# MFX.net
KiCad netlist of a schematic drawn in Altium Designer
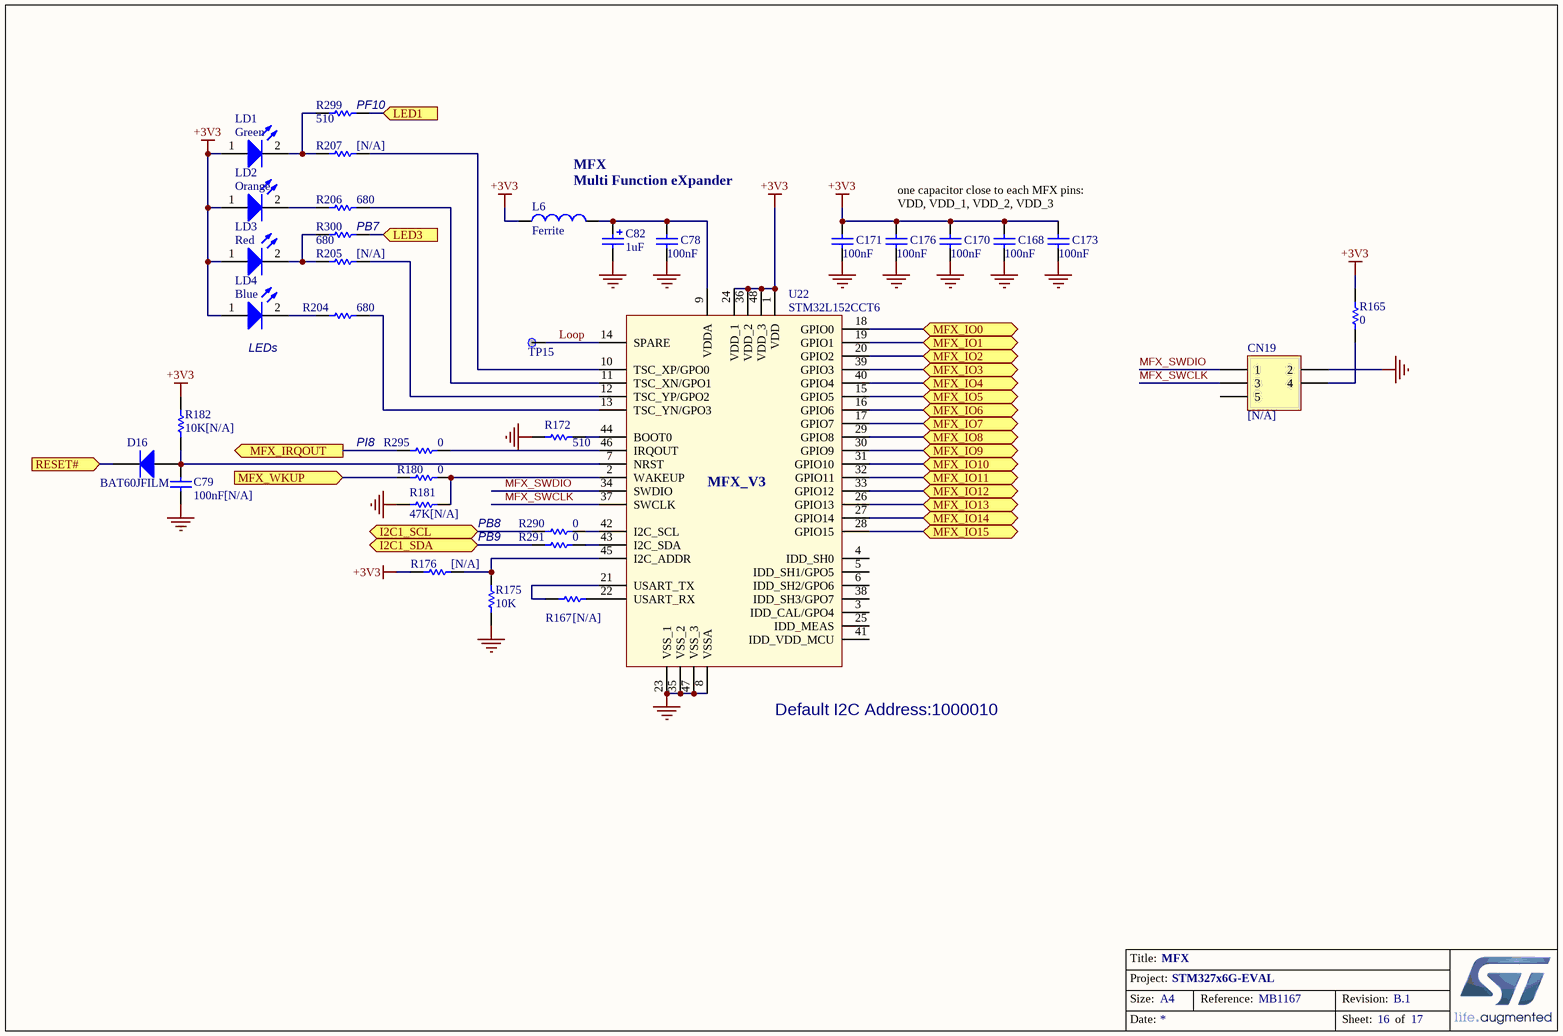
[diagram p0: MFX.SchDoc]

(export (version "E")
  (design (tool "Eeschema 10.0.6"))
  (components
    (comp (ref "C78")
      (value "100nF")
      (footprint "0402C")
      (description "Capacitor,100nF,16V,X7R,10%,0402,YAGEO")
      (libsource (lib "MCD_TOOLS") (part "Cap_100nF_X7R_10%_0402"))
    )
    (comp (ref "C79")
      (value "100nF[N/A]")
      (footprint "0402C")
      (description "Capacitor,100nF,16V,X7R,10%,0402,YAGEO")
      (libsource (lib "MCD_TOOLS") (part "Cap_100nF_X7R_10%_0402"))
    )
    (comp (ref "C82")
      (value "1uF")
      (footprint "TAN-A")
      (description "Polarized Capacitor,1uF,16V,10%,typeA,AVX")
      (libsource (lib "MCD_TOOLS") (part "Cap_1uF_POL_10%_TANA"))
    )
    (comp (ref "C168")
      (value "100nF")
      (footprint "0402C")
      (description "Capacitor,100nF,16V,X7R,10%,0402,YAGEO")
      (libsource (lib "MCD_TOOLS") (part "Cap_100nF_X7R_10%_0402"))
    )
    (comp (ref "C170")
      (value "100nF")
      (footprint "0402C")
      (description "Capacitor,100nF,16V,X7R,10%,0402,YAGEO")
      (libsource (lib "MCD_TOOLS") (part "Cap_100nF_X7R_10%_0402"))
    )
    (comp (ref "C171")
      (value "100nF")
      (footprint "0402C")
      (description "Capacitor,100nF,16V,X7R,10%,0402,YAGEO")
      (libsource (lib "MCD_TOOLS") (part "Cap_100nF_X7R_10%_0402"))
    )
    (comp (ref "C173")
      (value "100nF")
      (footprint "0402C")
      (description "Capacitor,100nF,16V,X7R,10%,0402,YAGEO")
      (libsource (lib "MCD_TOOLS") (part "Cap_100nF_X7R_10%_0402"))
    )
    (comp (ref "C176")
      (value "100nF")
      (footprint "0402C")
      (description "Capacitor,100nF,16V,X7R,10%,0402,YAGEO")
      (libsource (lib "MCD_TOOLS") (part "Cap_100nF_X7R_10%_0402"))
    )
    (comp (ref "CN19")
      (value "[N/A]")
      (footprint "HDR_2X3-1_2R54-6")
      (description "Header, 3-Pin, Dual row")
      (fields (field (name "PUBLISHER") "Altium Limited"))
      (libsource (lib "Miscellaneous Connectors") (part "Header 3X2"))
    )
    (comp (ref "D16")
      (value "BAT60JFILM")
      (footprint "SOD-323")
      (description "Default Diode")
      (fields (field (name "PUBLISHER") "Altium Limited"))
      (libsource (lib "Miscellaneous Devices") (part "Diode"))
    )
    (comp (ref "L6")
      (value "Ferrite")
      (footprint "0603L")
      (description "Bead,600R,350mA,0603,FCM1608KF-601T03,Tai-tech")
      (libsource (lib "MCD_TOOLS") (part "BEAD_600R_350MA_0603"))
    )
    (comp (ref "LD1")
      (value "Green")
      (footprint "0603D")
      (description "Typical RED, GREEN, YELLOW, AMBER GaAs LED")
      (fields (field (name "PUBLISHER") "Altium Limited"))
      (libsource (lib "Miscellaneous Devices") (part "LED2"))
    )
    (comp (ref "LD2")
      (value "Orange")
      (footprint "0603D")
      (description "Typical RED, GREEN, YELLOW, AMBER GaAs LED")
      (fields (field (name "PUBLISHER") "Altium Limited"))
      (libsource (lib "Miscellaneous Devices") (part "LED2"))
    )
    (comp (ref "LD3")
      (value "Red")
      (footprint "0603D")
      (description "Typical RED, GREEN, YELLOW, AMBER GaAs LED")
      (fields (field (name "PUBLISHER") "Altium Limited"))
      (libsource (lib "Miscellaneous Devices") (part "LED2"))
    )
    (comp (ref "LD4")
      (value "Blue")
      (footprint "0603D")
      (description "Typical RED, GREEN, YELLOW, AMBER GaAs LED")
      (fields (field (name "PUBLISHER") "Altium Limited"))
      (libsource (lib "Miscellaneous Devices") (part "LED2"))
    )
    (comp (ref "R165")
      (value "0")
      (footprint "0603R")
      (description "Resistor")
      (fields (field (name "PUBLISHER") "Altium Limited"))
      (libsource (lib "Miscellaneous Devices") (part "Res1"))
    )
    (comp (ref "R167")
      (value "[N/A]")
      (footprint "0603R")
      (description "Resistor")
      (fields (field (name "PUBLISHER") "Altium Limited"))
      (libsource (lib "Miscellaneous Devices") (part "res1"))
    )
    (comp (ref "R172")
      (value "510")
      (footprint "0402R")
      (description "Resistor 0402 or 0603 or 0805")
      (libsource (lib "MCD_TOOLS") (part "Resistor_ST"))
    )
    (comp (ref "R175")
      (value "10K")
      (footprint "0402R")
      (description "Resistor 0402 or 0603 or 0805")
      (libsource (lib "MCD_TOOLS") (part "Resistor_ST"))
    )
    (comp (ref "R176")
      (value "[N/A]")
      (footprint "0603R")
      (description "Resistor")
      (fields (field (name "PUBLISHER") "Altium Limited"))
      (libsource (lib "Miscellaneous Devices") (part "Res1"))
    )
    (comp (ref "R180")
      (value "0")
      (footprint "0603R")
      (description "Resistor")
      (fields (field (name "PUBLISHER") "Altium Limited"))
      (libsource (lib "Miscellaneous Devices") (part "Res1"))
    )
    (comp (ref "R181")
      (value "47K[N/A]")
      (footprint "0402R")
      (description "Resistor 0402 or 0603 or 0805")
      (libsource (lib "MCD_TOOLS") (part "Resistor_ST"))
    )
    (comp (ref "R182")
      (value "10K[N/A]")
      (footprint "0402R")
      (description "Resistor 0402 or 0603 or 0805")
      (libsource (lib "MCD_TOOLS") (part "Resistor_ST"))
    )
    (comp (ref "R204")
      (value "680")
      (footprint "0603R")
      (description "Resistor")
      (fields (field (name "PUBLISHER") "Altium Limited"))
      (libsource (lib "Miscellaneous Devices") (part "Res1"))
    )
    (comp (ref "R205")
      (value "[N/A]")
      (footprint "0603R")
      (description "Resistor")
      (fields (field (name "PUBLISHER") "Altium Limited"))
      (libsource (lib "Miscellaneous Devices") (part "Res1"))
    )
    (comp (ref "R206")
      (value "680")
      (footprint "0603R")
      (description "Resistor")
      (fields (field (name "PUBLISHER") "Altium Limited"))
      (libsource (lib "Miscellaneous Devices") (part "Res1"))
    )
    (comp (ref "R207")
      (value "[N/A]")
      (footprint "0603R")
      (description "Resistor")
      (fields (field (name "PUBLISHER") "Altium Limited"))
      (libsource (lib "Miscellaneous Devices") (part "Res1"))
    )
    (comp (ref "R290")
      (value "0")
      (footprint "0603R")
      (description "Resistor")
      (fields (field (name "PUBLISHER") "Altium Limited"))
      (libsource (lib "Miscellaneous Devices") (part "Res1"))
    )
    (comp (ref "R291")
      (value "0")
      (footprint "0603R")
      (description "Resistor")
      (fields (field (name "PUBLISHER") "Altium Limited"))
      (libsource (lib "Miscellaneous Devices") (part "Res1"))
    )
    (comp (ref "R295")
      (value "0")
      (footprint "0603R")
      (description "Resistor")
      (fields (field (name "PUBLISHER") "Altium Limited"))
      (libsource (lib "Miscellaneous Devices") (part "Res1"))
    )
    (comp (ref "R299")
      (value "510")
      (footprint "0603R")
      (description "Resistor")
      (fields (field (name "PUBLISHER") "Altium Limited"))
      (libsource (lib "Miscellaneous Devices") (part "Res1"))
    )
    (comp (ref "R300")
      (value "680")
      (footprint "0603R")
      (description "Resistor")
      (fields (field (name "PUBLISHER") "Altium Limited"))
      (libsource (lib "Miscellaneous Devices") (part "Res1"))
    )
    (comp (ref "TP15") (value "~") (footprint "TP") (libsource (lib "*") (part "TP")))
    (comp (ref "U22")
      (value "STM32L152CCT6")
      (footprint "LQFP48_0R5_9X9")
      (description "Multifunction expander")
      (libsource (lib "MB1167") (part "MFX"))
    )
  )
  (nets
    (net (code "1") (name "+3V3") (class "Default")
      (node (ref "C168") (pin "2") (pinfunction "2_2") (pintype "passive"))
      (node (ref "C170") (pin "1") (pinfunction "1_1") (pintype "passive"))
      (node (ref "C171") (pin "2") (pinfunction "2_2") (pintype "passive"))
      (node (ref "C173") (pin "2") (pinfunction "2_2") (pintype "passive"))
      (node (ref "C176") (pin "2") (pinfunction "2_2") (pintype "passive"))
      (node (ref "L6") (pin "1") (pinfunction "1_1") (pintype "passive"))
      (node (ref "LD1") (pin "1") (pinfunction "A_1") (pintype "passive"))
      (node (ref "LD2") (pin "1") (pinfunction "A_1") (pintype "passive"))
      (node (ref "LD3") (pin "1") (pinfunction "A_1") (pintype "passive"))
      (node (ref "LD4") (pin "1") (pinfunction "A_1") (pintype "passive"))
      (node (ref "R165") (pin "1") (pinfunction "1_1") (pintype "passive"))
      (node (ref "R176") (pin "2") (pinfunction "2_2") (pintype "passive"))
      (node (ref "R182") (pin "2") (pinfunction "2_2") (pintype "passive"))
      (node (ref "U22") (pin "1") (pinfunction "VDD_1") (pintype "passive"))
      (node (ref "U22") (pin "24") (pinfunction "VDD_1_24") (pintype "passive"))
      (node (ref "U22") (pin "36") (pinfunction "VDD_2_36") (pintype "passive"))
      (node (ref "U22") (pin "48") (pinfunction "VDD_3_48") (pintype "passive"))
    )
    (net (code "2") (name "/I2C1_SCL") (class "Default")
      (node (ref "R290") (pin "1") (pinfunction "1_1") (pintype "passive"))
    )
    (net (code "3") (name "/I2C1_SDA") (class "Default")
      (node (ref "R291") (pin "1") (pinfunction "1_1") (pintype "passive"))
    )
    (net (code "4") (name "/LED1") (class "Default")
      (node (ref "R299") (pin "1") (pinfunction "1_1") (pintype "passive"))
    )
    (net (code "5") (name "/LED3") (class "Default")
      (node (ref "R300") (pin "1") (pinfunction "1_1") (pintype "passive"))
    )
    (net (code "6") (name "/Loop") (class "Default")
      (node (ref "TP15") (pin "1") (pinfunction "1_1") (pintype "passive"))
      (node (ref "U22") (pin "14") (pinfunction "SPARE_14") (pintype "passive"))
    )
    (net (code "7") (name "/MFX_IO0") (class "Default")
      (node (ref "U22") (pin "18") (pinfunction "GPIO0_18") (pintype "passive"))
    )
    (net (code "8") (name "/MFX_IO1") (class "Default")
      (node (ref "U22") (pin "19") (pinfunction "GPIO1_19") (pintype "passive"))
    )
    (net (code "9") (name "/MFX_IO2") (class "Default")
      (node (ref "U22") (pin "20") (pinfunction "GPIO2_20") (pintype "passive"))
    )
    (net (code "10") (name "/MFX_IO3") (class "Default")
      (node (ref "U22") (pin "39") (pinfunction "GPIO3_39") (pintype "passive"))
    )
    (net (code "11") (name "/MFX_IO4") (class "Default")
      (node (ref "U22") (pin "40") (pinfunction "GPIO4_40") (pintype "passive"))
    )
    (net (code "12") (name "/MFX_IO5") (class "Default")
      (node (ref "U22") (pin "15") (pinfunction "GPIO5_15") (pintype "passive"))
    )
    (net (code "13") (name "/MFX_IO6") (class "Default")
      (node (ref "U22") (pin "16") (pinfunction "GPIO6_16") (pintype "passive"))
    )
    (net (code "14") (name "/MFX_IO7") (class "Default")
      (node (ref "U22") (pin "17") (pinfunction "GPIO7_17") (pintype "passive"))
    )
    (net (code "15") (name "/MFX_IO8") (class "Default")
      (node (ref "U22") (pin "29") (pinfunction "GPIO8_29") (pintype "passive"))
    )
    (net (code "16") (name "/MFX_IO9") (class "Default")
      (node (ref "U22") (pin "30") (pinfunction "GPIO9_30") (pintype "passive"))
    )
    (net (code "17") (name "/MFX_IO10") (class "Default")
      (node (ref "U22") (pin "31") (pinfunction "GPIO10_31") (pintype "passive"))
    )
    (net (code "18") (name "/MFX_IO11") (class "Default")
      (node (ref "U22") (pin "32") (pinfunction "GPIO11_32") (pintype "passive"))
    )
    (net (code "19") (name "/MFX_IO12") (class "Default")
      (node (ref "U22") (pin "33") (pinfunction "GPIO12_33") (pintype "passive"))
    )
    (net (code "20") (name "/MFX_IO13") (class "Default")
      (node (ref "U22") (pin "26") (pinfunction "GPIO13_26") (pintype "passive"))
    )
    (net (code "21") (name "/MFX_IO14") (class "Default")
      (node (ref "U22") (pin "27") (pinfunction "GPIO14_27") (pintype "passive"))
    )
    (net (code "22") (name "/MFX_IO15") (class "Default")
      (node (ref "U22") (pin "28") (pinfunction "GPIO15_28") (pintype "passive"))
    )
    (net (code "23") (name "/MFX_IRQOUT") (class "Default")
      (node (ref "R295") (pin "1") (pinfunction "1_1") (pintype "passive"))
    )
    (net (code "24") (name "/MFX_SWCLK") (class "Default")
      (node (ref "CN19") (pin "3") (pinfunction "3_3") (pintype "passive"))
      (node (ref "U22") (pin "37") (pinfunction "SWCLK_37") (pintype "passive"))
    )
    (net (code "25") (name "/MFX_SWDIO") (class "Default")
      (node (ref "CN19") (pin "1") (pinfunction "1_1") (pintype "passive"))
      (node (ref "U22") (pin "34") (pinfunction "SWDIO_34") (pintype "passive"))
    )
    (net (code "26") (name "/MFX_WKUP") (class "Default")
      (node (ref "R180") (pin "2") (pinfunction "2_2") (pintype "passive"))
    )
    (net (code "27") (name "/RESET#") (class "Default")
      (node (ref "D16") (pin "2") (pinfunction "K_2") (pintype "passive"))
    )
    (net (code "28") (name "GND") (class "Default")
      (node (ref "C168") (pin "1") (pinfunction "1_1") (pintype "passive"))
      (node (ref "C170") (pin "2") (pinfunction "2_2") (pintype "passive"))
      (node (ref "C171") (pin "1") (pinfunction "1_1") (pintype "passive"))
      (node (ref "C173") (pin "1") (pinfunction "1_1") (pintype "passive"))
      (node (ref "C176") (pin "1") (pinfunction "1_1") (pintype "passive"))
      (node (ref "C78") (pin "1") (pinfunction "1_1") (pintype "passive"))
      (node (ref "C79") (pin "1") (pinfunction "1_1") (pintype "passive"))
      (node (ref "C82") (pin "2") (pinfunction "2_2") (pintype "passive"))
      (node (ref "CN19") (pin "2") (pinfunction "2_2") (pintype "passive"))
      (node (ref "R172") (pin "2") (pinfunction "2_2") (pintype "passive"))
      (node (ref "R175") (pin "2") (pinfunction "2_2") (pintype "passive"))
      (node (ref "R181") (pin "1") (pinfunction "1_1") (pintype "passive"))
      (node (ref "U22") (pin "23") (pinfunction "VSS_1_23") (pintype "passive"))
      (node (ref "U22") (pin "35") (pinfunction "VSS_2_35") (pintype "passive"))
      (node (ref "U22") (pin "47") (pinfunction "VSS_3_47") (pintype "passive"))
      (node (ref "U22") (pin "8") (pinfunction "VSSA_8") (pintype "passive"))
    )
    (net (code "29") (name "Net-(CN19-Pad4)") (class "Default")
      (node (ref "CN19") (pin "4") (pinfunction "4_4") (pintype "passive"))
      (node (ref "R165") (pin "2") (pinfunction "2_2") (pintype "passive"))
    )
    (net (code "30") (name "Net-(D16-A)") (class "Default")
      (node (ref "C79") (pin "2") (pinfunction "2_2") (pintype "passive"))
      (node (ref "D16") (pin "1") (pinfunction "A_1") (pintype "passive"))
      (node (ref "R182") (pin "1") (pinfunction "1_1") (pintype "passive"))
      (node (ref "U22") (pin "7") (pinfunction "NRST_7") (pintype "passive"))
    )
    (net (code "31") (name "Net-(LD1-K)") (class "Default")
      (node (ref "LD1") (pin "2") (pinfunction "K_2") (pintype "passive"))
      (node (ref "R207") (pin "2") (pinfunction "2_2") (pintype "passive"))
      (node (ref "R299") (pin "2") (pinfunction "2_2") (pintype "passive"))
    )
    (net (code "32") (name "Net-(LD2-K)") (class "Default")
      (node (ref "LD2") (pin "2") (pinfunction "K_2") (pintype "passive"))
      (node (ref "R206") (pin "2") (pinfunction "2_2") (pintype "passive"))
    )
    (net (code "33") (name "Net-(LD3-K)") (class "Default")
      (node (ref "LD3") (pin "2") (pinfunction "K_2") (pintype "passive"))
      (node (ref "R205") (pin "2") (pinfunction "2_2") (pintype "passive"))
      (node (ref "R300") (pin "2") (pinfunction "2_2") (pintype "passive"))
    )
    (net (code "34") (name "Net-(LD4-K)") (class "Default")
      (node (ref "LD4") (pin "2") (pinfunction "K_2") (pintype "passive"))
      (node (ref "R204") (pin "2") (pinfunction "2_2") (pintype "passive"))
    )
    (net (code "35") (name "Net-(U22-BOOT0)") (class "Default")
      (node (ref "R172") (pin "1") (pinfunction "1_1") (pintype "passive"))
      (node (ref "U22") (pin "44") (pinfunction "BOOT0_44") (pintype "passive"))
    )
    (net (code "36") (name "Net-(U22-I2C_ADDR)") (class "Default")
      (node (ref "R175") (pin "1") (pinfunction "1_1") (pintype "passive"))
      (node (ref "R176") (pin "1") (pinfunction "1_1") (pintype "passive"))
      (node (ref "U22") (pin "45") (pinfunction "I2C_ADDR_45") (pintype "passive"))
    )
    (net (code "37") (name "Net-(U22-I2C_SCL)") (class "Default")
      (node (ref "R290") (pin "2") (pinfunction "2_2") (pintype "passive"))
      (node (ref "U22") (pin "42") (pinfunction "I2C_SCL_42") (pintype "passive"))
    )
    (net (code "38") (name "Net-(U22-I2C_SDA)") (class "Default")
      (node (ref "R291") (pin "2") (pinfunction "2_2") (pintype "passive"))
      (node (ref "U22") (pin "43") (pinfunction "I2C_SDA_43") (pintype "passive"))
    )
    (net (code "39") (name "Net-(U22-IRQOUT)") (class "Default")
      (node (ref "R295") (pin "2") (pinfunction "2_2") (pintype "passive"))
      (node (ref "U22") (pin "46") (pinfunction "IRQOUT_46") (pintype "passive"))
    )
    (net (code "40") (name "Net-(U22-TSC_XN{slash}GPO1)") (class "Default")
      (node (ref "R206") (pin "1") (pinfunction "1_1") (pintype "passive"))
      (node (ref "U22") (pin "11") (pinfunction "TSC_XN/GPO1_11") (pintype "passive"))
    )
    (net (code "41") (name "Net-(U22-TSC_XP{slash}GPO0)") (class "Default")
      (node (ref "R207") (pin "1") (pinfunction "1_1") (pintype "passive"))
      (node (ref "U22") (pin "10") (pinfunction "TSC_XP/GPO0_10") (pintype "passive"))
    )
    (net (code "42") (name "Net-(U22-TSC_YN{slash}GPO3)") (class "Default")
      (node (ref "R204") (pin "1") (pinfunction "1_1") (pintype "passive"))
      (node (ref "U22") (pin "13") (pinfunction "TSC_YN/GPO3_13") (pintype "passive"))
    )
    (net (code "43") (name "Net-(U22-TSC_YP{slash}GPO2)") (class "Default")
      (node (ref "R205") (pin "1") (pinfunction "1_1") (pintype "passive"))
      (node (ref "U22") (pin "12") (pinfunction "TSC_YP/GPO2_12") (pintype "passive"))
    )
    (net (code "44") (name "Net-(U22-USART_RX)") (class "Default")
      (node (ref "R167") (pin "2") (pinfunction "2_2") (pintype "passive"))
      (node (ref "U22") (pin "22") (pinfunction "USART_RX_22") (pintype "passive"))
    )
    (net (code "45") (name "Net-(U22-USART_TX)") (class "Default")
      (node (ref "R167") (pin "1") (pinfunction "1_1") (pintype "passive"))
      (node (ref "U22") (pin "21") (pinfunction "USART_TX_21") (pintype "passive"))
    )
    (net (code "46") (name "Net-(U22-VDDA)") (class "Default")
      (node (ref "C78") (pin "2") (pinfunction "2_2") (pintype "passive"))
      (node (ref "C82") (pin "1") (pinfunction "1_1") (pintype "passive"))
      (node (ref "L6") (pin "2") (pinfunction "2_2") (pintype "passive"))
      (node (ref "U22") (pin "9") (pinfunction "VDDA_9") (pintype "passive"))
    )
    (net (code "47") (name "Net-(U22-WAKEUP)") (class "Default")
      (node (ref "R180") (pin "1") (pinfunction "1_1") (pintype "passive"))
      (node (ref "R181") (pin "2") (pinfunction "2_2") (pintype "passive"))
      (node (ref "U22") (pin "2") (pinfunction "WAKEUP_2") (pintype "passive"))
    )
    (net (code "48") (name "unconnected-(CN19-Pad5)") (class "Default")
      (node (ref "CN19") (pin "5") (pinfunction "5_5") (pintype "passive"))
    )
    (net (code "49") (name "unconnected-(U22-IDD_CAL{slash}GPO4-Pad3)") (class "Default")
      (node (ref "U22") (pin "3") (pinfunction "IDD_CAL/GPO4_3") (pintype "passive"))
    )
    (net (code "50") (name "unconnected-(U22-IDD_MEAS-Pad25)") (class "Default")
      (node (ref "U22") (pin "25") (pinfunction "IDD_MEAS_25") (pintype "passive"))
    )
    (net (code "51") (name "unconnected-(U22-IDD_SH0-Pad4)") (class "Default")
      (node (ref "U22") (pin "4") (pinfunction "IDD_SH0_4") (pintype "passive"))
    )
    (net (code "52") (name "unconnected-(U22-IDD_SH1{slash}GPO5-Pad5)") (class "Default")
      (node (ref "U22") (pin "5") (pinfunction "IDD_SH1/GPO5_5") (pintype "passive"))
    )
    (net (code "53") (name "unconnected-(U22-IDD_SH2{slash}GPO6-Pad6)") (class "Default")
      (node (ref "U22") (pin "6") (pinfunction "IDD_SH2/GPO6_6") (pintype "passive"))
    )
    (net (code "54") (name "unconnected-(U22-IDD_SH3{slash}GPO7-Pad38)") (class "Default")
      (node (ref "U22") (pin "38") (pinfunction "IDD_SH3/GPO7_38") (pintype "passive"))
    )
    (net (code "55") (name "unconnected-(U22-IDD_VDD_MCU-Pad41)") (class "Default")
      (node (ref "U22") (pin "41") (pinfunction "IDD_VDD_MCU_41") (pintype "passive"))
    )
  )
)
